# Charmware_Star.net
KiCad netlist of a schematic drawn in EAGLE
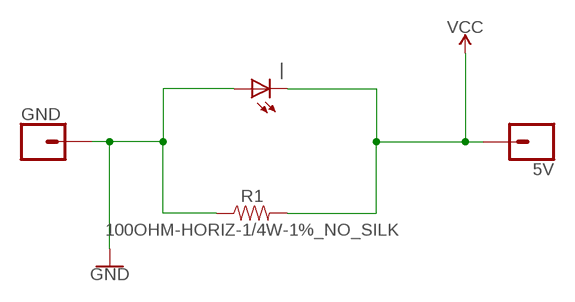
[diagram p0: schematic, sheet 1]

(export (version "E")
  (design (tool "Eeschema 10.0.6"))
  (components
    (comp (ref "5V")
      (value "CONN_01PTH_NO_SILK_YES_STOP")
      (footprint "eagle-import:1X01_NO_SILK")
      (libsource (lib "eagle-import") (part "CONN_01PTH_NO_SILK_YES_STOP"))
    )
    (comp (ref "GND")
      (value "CONN_01PTH_NO_SILK_YES_STOP")
      (footprint "eagle-import:1X01_NO_SILK")
      (libsource (lib "eagle-import") (part "CONN_01PTH_NO_SILK_YES_STOP"))
    )
    (comp (ref "R1")
      (value "100OHM-HORIZ-1/4W-1%_NO_SILK")
      (footprint "eagle-import:AXIAL-0.3-NO_SILK")
      (libsource (lib "eagle-import") (part "100OHM-HORIZ-1/4W-1%_NO_SILK"))
    )
    (comp (ref "|")
      (value "LEDSMT1206")
      (footprint "eagle-import:1206")
      (libsource (lib "eagle-import") (part "LEDSMT1206"))
    )
  )
  (nets
    (net (code "1") (name "GND") (class "Default")
      (node (ref "GND") (pin "1") (pinfunction "1_1") (pintype "passive"))
      (node (ref "R1") (pin "P$1") (pinfunction "1_P$1") (pintype "passive"))
      (node (ref "|") (pin "A") (pinfunction "A_A") (pintype "passive"))
    )
    (net (code "2") (name "VCC") (class "Default")
      (node (ref "5V") (pin "1") (pinfunction "1_1") (pintype "passive"))
      (node (ref "R1") (pin "P$2") (pinfunction "2_P$2") (pintype "passive"))
      (node (ref "|") (pin "C") (pinfunction "C_C") (pintype "passive"))
    )
  )
)
